# CANBusTerminator.net
KiCad netlist of a schematic drawn in EasyEDA Pro
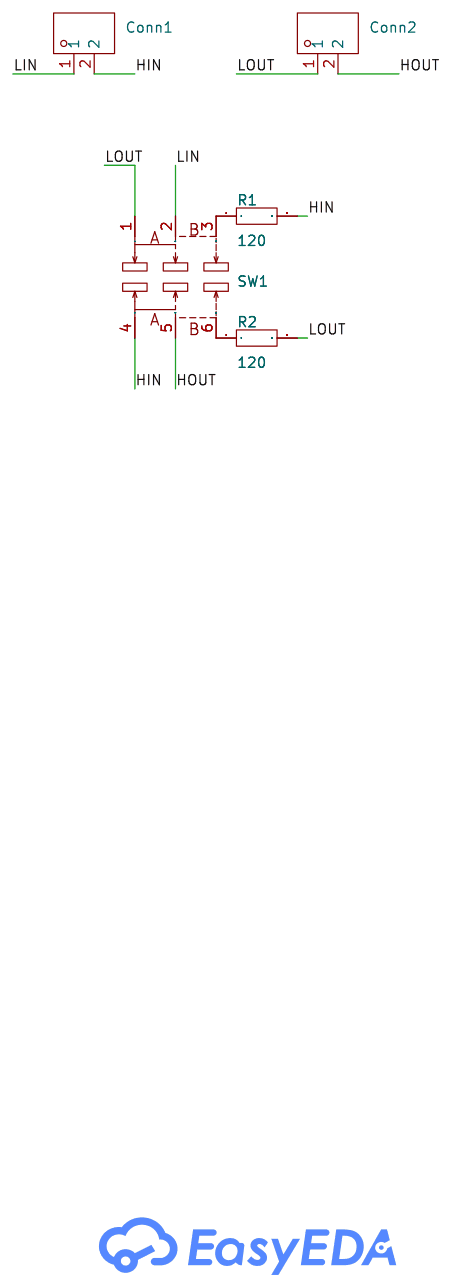
[diagram p0: schematic sheet]

(export (version "E")
  (design (tool "Eeschema 10.0.6"))
  (components
    (comp (ref "Conn1")
      (value "HDGC4001SMD-S-2P")
      (footprint "easyedapro:CONN-SMD_2P-P4.00_HDGC4001SMD-S-2P")
      (fields (field (name "Manufacturer") "HDGC(华德共创)"))
      (libsource (lib "easyedapro") (part "HDGC4001SMD-S-2P"))
    )
    (comp (ref "Conn2")
      (value "HDGC4001SMD-S-2P")
      (footprint "easyedapro:CONN-SMD_2P-P4.00_HDGC4001SMD-S-2P")
      (fields (field (name "Manufacturer") "HDGC(华德共创)"))
      (libsource (lib "easyedapro") (part "HDGC4001SMD-S-2P"))
    )
    (comp (ref "R1") (value "120") (footprint "easyedapro:R0603") (libsource (lib "easyedapro") (part "Res")))
    (comp (ref "R2") (value "120") (footprint "easyedapro:R0603") (libsource (lib "easyedapro") (part "Res")))
    (comp (ref "SW1")
      (value "MST22D18G2 125")
      (footprint "easyedapro:SW-SMD_MST22D18G2")
      (fields (field (name "Manufacturer") "SHOU HAN(首韩)"))
      (libsource (lib "easyedapro") (part "MST22D18G2 125"))
    )
  )
  (nets
    (net (code "1") (name "/HIN") (class "Default")
      (node (ref "Conn1") (pin "2") (pinfunction "2_2") (pintype "unspecified"))
      (node (ref "R1") (pin "2") (pinfunction "2_2") (pintype "input"))
      (node (ref "SW1") (pin "4") (pinfunction "4_4") (pintype "unspecified"))
    )
    (net (code "2") (name "/HOUT") (class "Default")
      (node (ref "Conn2") (pin "2") (pinfunction "2_2") (pintype "unspecified"))
      (node (ref "SW1") (pin "5") (pinfunction "5_5") (pintype "unspecified"))
    )
    (net (code "3") (name "/LIN") (class "Default")
      (node (ref "Conn1") (pin "1") (pinfunction "1_1") (pintype "unspecified"))
      (node (ref "SW1") (pin "2") (pinfunction "2_2") (pintype "unspecified"))
    )
    (net (code "4") (name "/LOUT") (class "Default")
      (node (ref "Conn2") (pin "1") (pinfunction "1_1") (pintype "unspecified"))
      (node (ref "R2") (pin "2") (pinfunction "2_2") (pintype "input"))
      (node (ref "SW1") (pin "1") (pinfunction "1_1") (pintype "unspecified"))
    )
    (net (code "5") (name "Net-(R1-Pad1)") (class "Default")
      (node (ref "R1") (pin "1") (pinfunction "1_1") (pintype "input"))
      (node (ref "SW1") (pin "3") (pinfunction "3_3") (pintype "unspecified"))
    )
    (net (code "6") (name "Net-(R2-Pad1)") (class "Default")
      (node (ref "R2") (pin "1") (pinfunction "1_1") (pintype "input"))
      (node (ref "SW1") (pin "6") (pinfunction "6_6") (pintype "unspecified"))
    )
  )
)
